# PSU.net
KiCad netlist of a schematic drawn in EAGLE
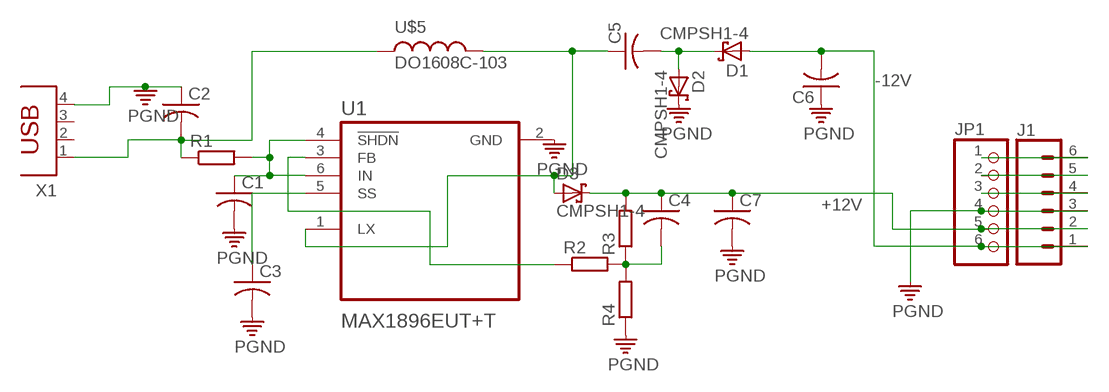
[diagram p0: schematic, sheet 1]

(export (version "E")
  (design (tool "Eeschema 10.0.6"))
  (components
    (comp (ref "C1")
      (value "C-US025-025X050")
      (footprint "eagle-import:C025-025X050")
      (libsource (lib "eagle-import") (part "C-US025-025X050"))
    )
    (comp (ref "C2")
      (value "C-US025-025X050")
      (footprint "eagle-import:C025-025X050")
      (libsource (lib "eagle-import") (part "C-US025-025X050"))
    )
    (comp (ref "C3")
      (value "C-US025-025X050")
      (footprint "eagle-import:C025-025X050")
      (libsource (lib "eagle-import") (part "C-US025-025X050"))
    )
    (comp (ref "C4")
      (value "C-US025-025X050")
      (footprint "eagle-import:C025-025X050")
      (libsource (lib "eagle-import") (part "C-US025-025X050"))
    )
    (comp (ref "C5")
      (value "C-US025-025X050")
      (footprint "eagle-import:C025-025X050")
      (libsource (lib "eagle-import") (part "C-US025-025X050"))
    )
    (comp (ref "C6")
      (value "C-US025-025X050")
      (footprint "eagle-import:C025-025X050")
      (libsource (lib "eagle-import") (part "C-US025-025X050"))
    )
    (comp (ref "C7")
      (value "C-US025-025X050")
      (footprint "eagle-import:C025-025X050")
      (libsource (lib "eagle-import") (part "C-US025-025X050"))
    )
    (comp (ref "D1")
      (value "CMPSH1-4")
      (footprint "eagle-import:SOT23")
      (libsource (lib "eagle-import") (part "BAS70"))
    )
    (comp (ref "D2")
      (value "CMPSH1-4")
      (footprint "eagle-import:SOT23")
      (libsource (lib "eagle-import") (part "BAS70"))
    )
    (comp (ref "D3")
      (value "CMPSH1-4")
      (footprint "eagle-import:SOT23")
      (libsource (lib "eagle-import") (part "BAS70"))
    )
    (comp (ref "J1")
      (value "CONN_06SMD-FEMALE-V2")
      (footprint "eagle-import:1X06-SMD-FEMALE")
      (libsource (lib "eagle-import") (part "CONN_06SMD-FEMALE-V2"))
    )
    (comp (ref "JP1")
      (value "PINHD-1X6/90")
      (footprint "eagle-import:1X06_90")
      (libsource (lib "eagle-import") (part "PINHD-1X6/90"))
    )
    (comp (ref "R1")
      (value "R-EU_0309/10")
      (footprint "eagle-import:0309_10")
      (libsource (lib "eagle-import") (part "R-EU_0309/10"))
    )
    (comp (ref "R2")
      (value "R-EU_0309/10")
      (footprint "eagle-import:0309_10")
      (libsource (lib "eagle-import") (part "R-EU_0309/10"))
    )
    (comp (ref "R3")
      (value "R-EU_0309/10")
      (footprint "eagle-import:0309_10")
      (libsource (lib "eagle-import") (part "R-EU_0309/10"))
    )
    (comp (ref "R4")
      (value "R-EU_0309/10")
      (footprint "eagle-import:0309_10")
      (libsource (lib "eagle-import") (part "R-EU_0309/10"))
    )
    (comp (ref "U$5")
      (value "DO1608C-103")
      (footprint "eagle-import:MSS1260")
      (libsource (lib "eagle-import") (part "MSS1260"))
    )
    (comp (ref "U1")
      (value "MAX1896EUT+T")
      (footprint "eagle-import:SOT95P280X145-6N")
      (fields (field (name "DIGI-KEY_PART_NUMBER") "MAX1896EUT+T-ND") (field (name "MF") "Maxim Integrated"))
      (libsource (lib "eagle-import") (part "MAX1896EUT+T"))
    )
    (comp (ref "X1")
      (value "PN61729")
      (footprint "eagle-import:PN61729")
      (libsource (lib "eagle-import") (part "PN61729"))
    )
  )
  (nets
    (net (code "1") (name "/+12V") (class "Default")
      (node (ref "C4") (pin "1") (pinfunction "1_1") (pintype "passive"))
      (node (ref "C7") (pin "1") (pinfunction "1_1") (pintype "passive"))
      (node (ref "D3") (pin "3") (pinfunction "C_3") (pintype "passive"))
      (node (ref "J1") (pin "2") (pinfunction "2_2") (pintype "passive"))
      (node (ref "JP1") (pin "5") (pinfunction "5_5") (pintype "passive"))
      (node (ref "R3") (pin "2") (pinfunction "2_2") (pintype "passive"))
    )
    (net (code "2") (name "/-12V") (class "Default")
      (node (ref "C6") (pin "2") (pinfunction "2_2") (pintype "passive"))
      (node (ref "D1") (pin "1") (pinfunction "A_1") (pintype "passive"))
      (node (ref "J1") (pin "1") (pinfunction "1_1") (pintype "passive"))
      (node (ref "JP1") (pin "6") (pinfunction "6_6") (pintype "passive"))
    )
    (net (code "3") (name "Net-(C2-Pad2)") (class "Default")
      (node (ref "C2") (pin "2") (pinfunction "2_2") (pintype "passive"))
      (node (ref "R1") (pin "1") (pinfunction "1_1") (pintype "passive"))
      (node (ref "U$5") (pin "P$2") (pinfunction "P$2_P$2") (pintype "passive"))
      (node (ref "X1") (pin "1") (pinfunction "1_1") (pintype "passive"))
    )
    (net (code "4") (name "Net-(C4-Pad2)") (class "Default")
      (node (ref "C4") (pin "2") (pinfunction "2_2") (pintype "passive"))
      (node (ref "R2") (pin "2") (pinfunction "2_2") (pintype "passive"))
      (node (ref "R3") (pin "1") (pinfunction "1_1") (pintype "passive"))
      (node (ref "R4") (pin "2") (pinfunction "2_2") (pintype "passive"))
    )
    (net (code "5") (name "Net-(D1-C)") (class "Default")
      (node (ref "C5") (pin "2") (pinfunction "2_2") (pintype "passive"))
      (node (ref "D1") (pin "3") (pinfunction "C_3") (pintype "passive"))
      (node (ref "D2") (pin "1") (pinfunction "A_1") (pintype "passive"))
    )
    (net (code "6") (name "Net-(D3-A)") (class "Default")
      (node (ref "C5") (pin "1") (pinfunction "1_1") (pintype "passive"))
      (node (ref "D3") (pin "1") (pinfunction "A_1") (pintype "passive"))
      (node (ref "U$5") (pin "P$1") (pinfunction "P$1_P$1") (pintype "passive"))
      (node (ref "U1") (pin "1") (pinfunction "LX_1") (pintype "bidirectional"))
    )
    (net (code "7") (name "Net-(J1-Pad4)") (class "Default")
      (node (ref "J1") (pin "4") (pinfunction "4_4") (pintype "passive"))
      (node (ref "JP1") (pin "3") (pinfunction "3_3") (pintype "passive"))
    )
    (net (code "8") (name "Net-(J1-Pad5)") (class "Default")
      (node (ref "J1") (pin "5") (pinfunction "5_5") (pintype "passive"))
      (node (ref "JP1") (pin "2") (pinfunction "2_2") (pintype "passive"))
    )
    (net (code "9") (name "Net-(J1-Pad6)") (class "Default")
      (node (ref "J1") (pin "6") (pinfunction "6_6") (pintype "passive"))
      (node (ref "JP1") (pin "1") (pinfunction "1_1") (pintype "passive"))
    )
    (net (code "10") (name "Net-(U1-FB)") (class "Default")
      (node (ref "R2") (pin "1") (pinfunction "1_1") (pintype "passive"))
      (node (ref "U1") (pin "3") (pinfunction "FB_3") (pintype "input"))
    )
    (net (code "11") (name "Net-(U1-IN)") (class "Default")
      (node (ref "C1") (pin "1") (pinfunction "1_1") (pintype "passive"))
      (node (ref "R1") (pin "2") (pinfunction "2_2") (pintype "passive"))
      (node (ref "U1") (pin "4") (pinfunction "~{SHDN}_4") (pintype "input"))
      (node (ref "U1") (pin "6") (pinfunction "IN_6") (pintype "input"))
    )
    (net (code "12") (name "Net-(U1-SS)") (class "Default")
      (node (ref "C3") (pin "1") (pinfunction "1_1") (pintype "passive"))
      (node (ref "U1") (pin "5") (pinfunction "SS_5") (pintype "input"))
    )
    (net (code "13") (name "PGND") (class "Default")
      (node (ref "C1") (pin "2") (pinfunction "2_2") (pintype "passive"))
      (node (ref "C2") (pin "1") (pinfunction "1_1") (pintype "passive"))
      (node (ref "C3") (pin "2") (pinfunction "2_2") (pintype "passive"))
      (node (ref "C6") (pin "1") (pinfunction "1_1") (pintype "passive"))
      (node (ref "C7") (pin "2") (pinfunction "2_2") (pintype "passive"))
      (node (ref "D2") (pin "3") (pinfunction "C_3") (pintype "passive"))
      (node (ref "J1") (pin "3") (pinfunction "3_3") (pintype "passive"))
      (node (ref "JP1") (pin "4") (pinfunction "4_4") (pintype "passive"))
      (node (ref "R4") (pin "1") (pinfunction "1_1") (pintype "passive"))
      (node (ref "U1") (pin "2") (pinfunction "GND_2") (pintype "power_in"))
      (node (ref "X1") (pin "4") (pinfunction "4_4") (pintype "passive"))
    )
    (net (code "14") (name "unconnected-(X1-Pad2)") (class "Default")
      (node (ref "X1") (pin "2") (pinfunction "2_2") (pintype "passive"))
    )
    (net (code "15") (name "unconnected-(X1-Pad3)") (class "Default")
      (node (ref "X1") (pin "3") (pinfunction "3_3") (pintype "passive"))
    )
  )
)
